# Power_v2.net
KiCad netlist of a schematic drawn in Altium Designer
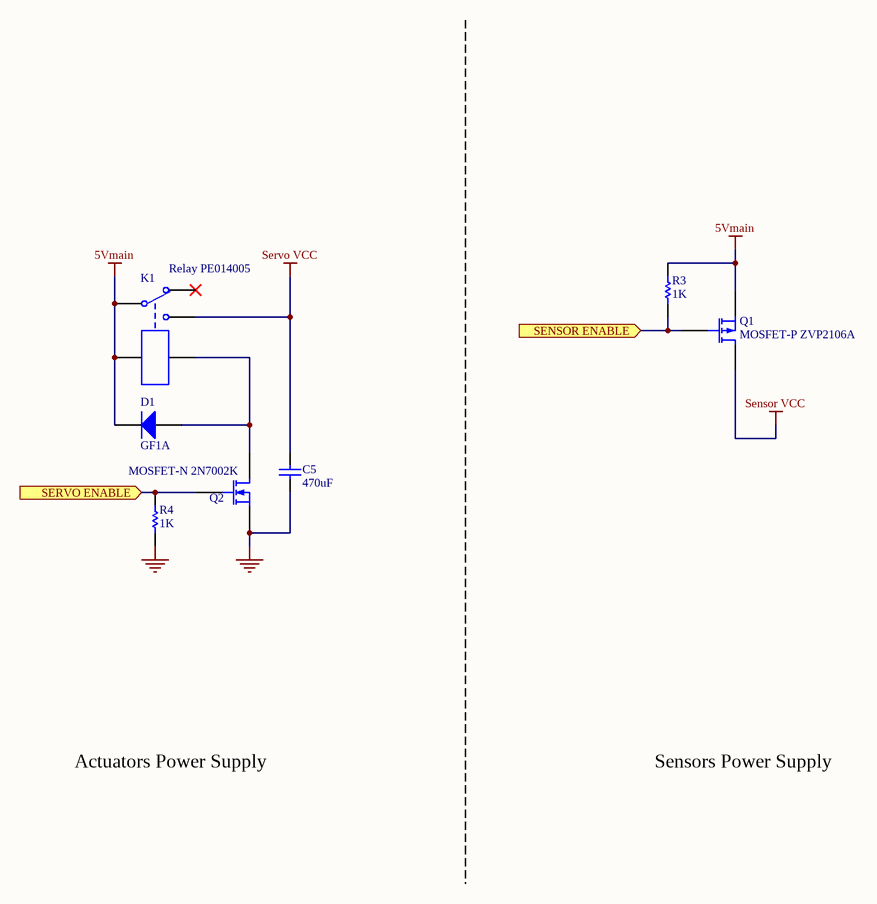
[diagram p0: Power_v2.SchDoc]

(export (version "E")
  (design (tool "Eeschema 10.0.6"))
  (components
    (comp (ref "C5")
      (value "470uF")
      (footprint "MarvinPcbLib2:CONDO_D_10mm")
      (description "Capacitor")
      (fields (field (name "PUBLISHER") "Altium Limited"))
      (libsource (lib "Miscellaneous Devices") (part "Cap"))
    )
    (comp (ref "D1")
      (value "GF1A")
      (footprint "SMA/DO-214AC_21")
      (description "Default Diode")
      (fields (field (name "PUBLISHER") "Altium Limited"))
      (libsource (lib "Miscellaneous Devices") (part "Diode"))
    )
    (comp (ref "K1")
      (value "Relay PE014005")
      (footprint "MarvinPcbLib2:PE014005")
      (description "Relay")
      (fields (field (name "PUBLISHER") "Altium Limited"))
      (libsource (lib "Miscellaneous Devices") (part "Relay-SPDT"))
    )
    (comp (ref "Q1")
      (value "MOSFET-P ZVP2106A")
      (footprint "SOT23")
      (description "P-Channel MOSFET")
      (fields (field (name "PUBLISHER") "Altium Limited"))
      (libsource (lib "Miscellaneous Devices") (part "MOSFET-P"))
    )
    (comp (ref "Q2")
      (value "MOSFET-N 2N7002K")
      (footprint "SOT23")
      (description "N-Channel MOSFET")
      (fields (field (name "PUBLISHER") "Altium Limited"))
      (libsource (lib "Miscellaneous Devices") (part "MOSFET-N"))
    )
    (comp (ref "R3")
      (value "1K")
      (footprint "1608 / 0603")
      (description "Resistor")
      (fields (field (name "PUBLISHER") "Altium Limited"))
      (libsource (lib "Miscellaneous Devices") (part "Res1"))
    )
    (comp (ref "R4")
      (value "1K")
      (footprint "1608 / 0603")
      (description "Resistor")
      (fields (field (name "PUBLISHER") "Altium Limited"))
      (libsource (lib "Miscellaneous Devices") (part "Res1"))
    )
  )
  (nets
    (net (code "1") (name "/SENSOR ENABLE") (class "Default")
      (node (ref "Q1") (pin "2") (pinfunction "G_2") (pintype "passive"))
      (node (ref "R3") (pin "1") (pinfunction "1_1") (pintype "passive"))
    )
    (net (code "2") (name "/SERVO ENABLE") (class "Default")
      (node (ref "Q2") (pin "1") (pinfunction "D_1") (pintype "passive"))
      (node (ref "R4") (pin "2") (pinfunction "2_2") (pintype "passive"))
    )
    (net (code "3") (name "5Vmain") (class "Default")
      (node (ref "D1") (pin "2") (pinfunction "K_2") (pintype "passive"))
      (node (ref "K1") (pin "12") (pinfunction "12_12") (pintype "passive"))
      (node (ref "K1") (pin "A2") (pinfunction "A2_A2") (pintype "passive"))
      (node (ref "Q1") (pin "3") (pinfunction "S_3") (pintype "passive"))
      (node (ref "R3") (pin "2") (pinfunction "2_2") (pintype "passive"))
    )
    (net (code "4") (name "GND") (class "Default")
      (node (ref "C5") (pin "1") (pinfunction "1_1") (pintype "passive"))
      (node (ref "Q2") (pin "2") (pinfunction "G_2") (pintype "passive"))
      (node (ref "R4") (pin "1") (pinfunction "1_1") (pintype "passive"))
    )
    (net (code "5") (name "Net-(D1-A)") (class "Default")
      (node (ref "D1") (pin "1") (pinfunction "A_1") (pintype "passive"))
      (node (ref "K1") (pin "A1") (pinfunction "A1_A1") (pintype "passive"))
      (node (ref "Q2") (pin "3") (pinfunction "S_3") (pintype "passive"))
    )
    (net (code "6") (name "Sensor VCC") (class "Default")
      (node (ref "Q1") (pin "1") (pinfunction "D_1") (pintype "passive"))
    )
    (net (code "7") (name "Servo VCC") (class "Default")
      (node (ref "C5") (pin "2") (pinfunction "2_2") (pintype "passive"))
      (node (ref "K1") (pin "11") (pinfunction "11_11") (pintype "passive"))
    )
    (net (code "8") (name "unconnected-(K1-Pad14)") (class "Default")
      (node (ref "K1") (pin "14") (pinfunction "14_14") (pintype "passive+no_connect"))
    )
  )
)
